# M_D_ext_power_8_0_1.net
KiCad netlist of a schematic drawn in EAGLE
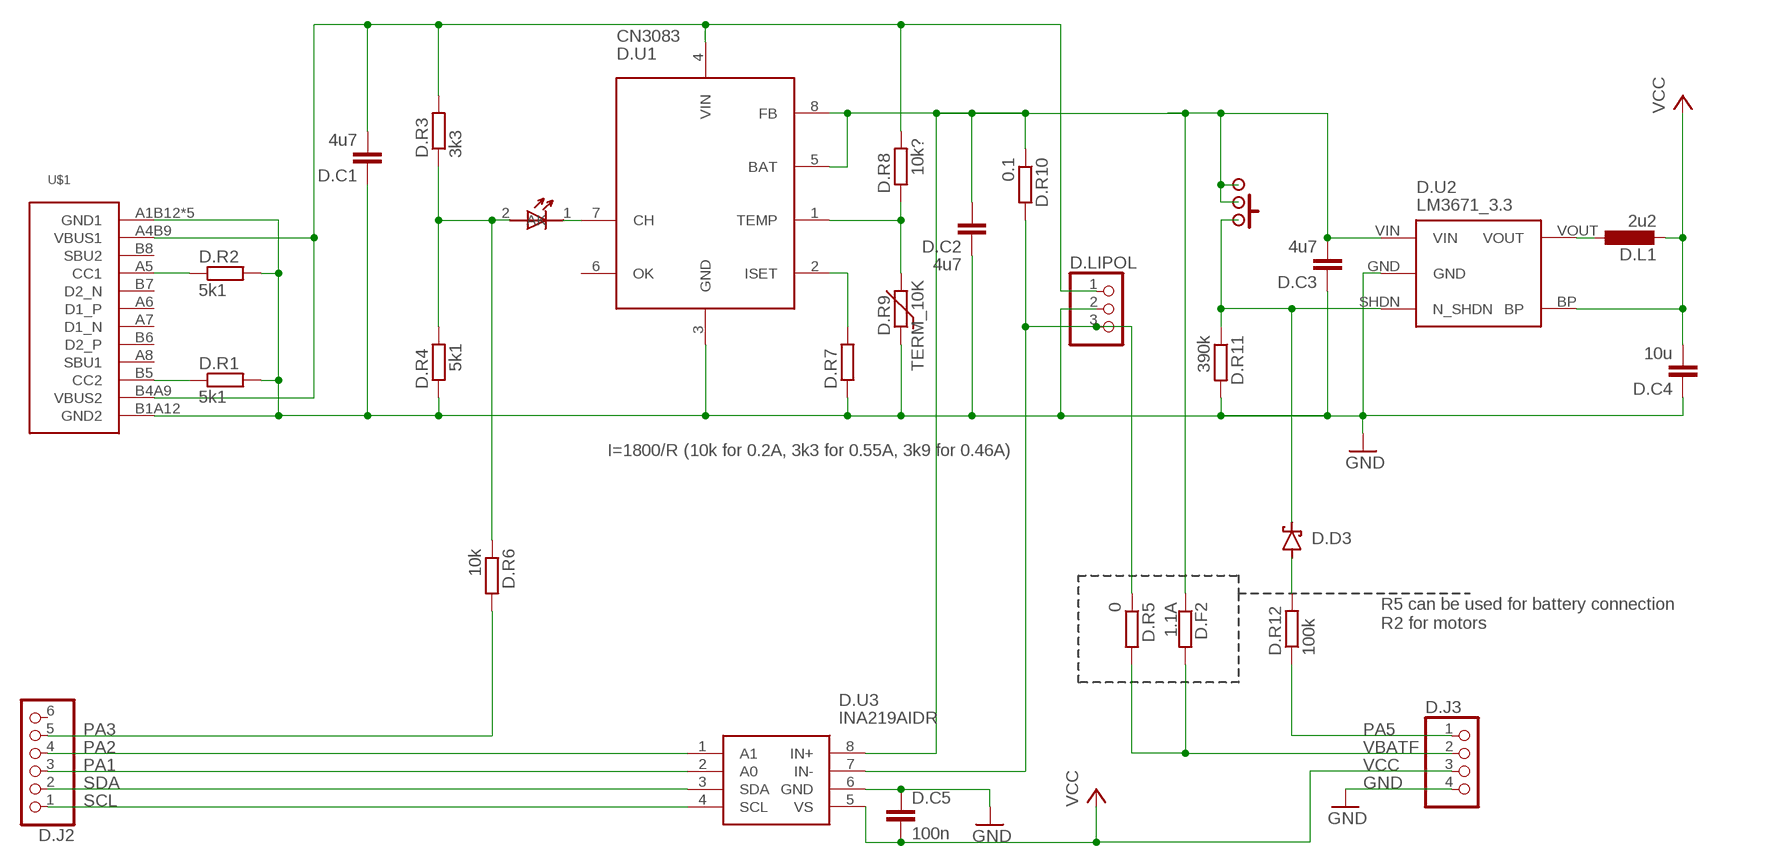
[diagram p0: schematic, sheet 1]

(export (version "E")
  (design (tool "Eeschema 10.0.6"))
  (components
    (comp (ref "D.C1")
      (value "4u7")
      (footprint "eagle-import:C0603")
      (libsource (lib "eagle-import") (part "C-EUC0603"))
    )
    (comp (ref "D.C2")
      (value "4u7")
      (footprint "eagle-import:C0603")
      (libsource (lib "eagle-import") (part "C-EUC0603"))
    )
    (comp (ref "D.C3")
      (value "4u7")
      (footprint "eagle-import:C0603")
      (libsource (lib "eagle-import") (part "C-EUC0603"))
    )
    (comp (ref "D.C4")
      (value "10u")
      (footprint "eagle-import:C0805")
      (libsource (lib "eagle-import") (part "C-EUC0805"))
    )
    (comp (ref "D.C5")
      (value "100n")
      (footprint "eagle-import:C0603")
      (libsource (lib "eagle-import") (part "C-EUC0603"))
    )
    (comp (ref "D.D1")
      (value "LED_1.8")
      (footprint "eagle-import:LED_1.8")
      (libsource (lib "eagle-import") (part "LED_1.8"))
    )
    (comp (ref "D.D3")
      (value "SHOTKY_2.8")
      (footprint "eagle-import:SHOTKY_2.8")
      (libsource (lib "eagle-import") (part "SHOTKY_2.8"))
    )
    (comp (ref "D.F2")
      (value "1.1A")
      (footprint "eagle-import:R0805")
      (libsource (lib "eagle-import") (part "R-EU_R0805"))
    )
    (comp (ref "D.J2")
      (value "PINHD-1X6")
      (footprint "eagle-import:1X06")
      (libsource (lib "eagle-import") (part "PINHD-1X6"))
    )
    (comp (ref "D.J3")
      (value "PINHD-1X4")
      (footprint "eagle-import:1X04")
      (libsource (lib "eagle-import") (part "PINHD-1X4"))
    )
    (comp (ref "D.L1")
      (value "2u2")
      (footprint "eagle-import:L3230M")
      (libsource (lib "eagle-import") (part "L-EUL3230M"))
    )
    (comp (ref "D.LIPOL")
      (value "PINHEAD-1X3-2")
      (footprint "eagle-import:1X-03-2")
      (libsource (lib "eagle-import") (part "PINHEAD-1X3-2"))
    )
    (comp (ref "D.ON/OFF/RESET")
      (value "SWITCH")
      (footprint "eagle-import:SWITCH")
      (libsource (lib "eagle-import") (part "SWITCH"))
    )
    (comp (ref "D.R1")
      (value "5k1")
      (footprint "eagle-import:R0603")
      (libsource (lib "eagle-import") (part "R-EU_R0603"))
    )
    (comp (ref "D.R2")
      (value "5k1")
      (footprint "eagle-import:R0603")
      (libsource (lib "eagle-import") (part "R-EU_R0603"))
    )
    (comp (ref "D.R3")
      (value "3k3")
      (footprint "eagle-import:R0603")
      (libsource (lib "eagle-import") (part "R-EU_R0603"))
    )
    (comp (ref "D.R4")
      (value "5k1")
      (footprint "eagle-import:R0603")
      (libsource (lib "eagle-import") (part "R-EU_R0603"))
    )
    (comp (ref "D.R5")
      (value "0")
      (footprint "eagle-import:R0603")
      (libsource (lib "eagle-import") (part "R-EU_R0603"))
    )
    (comp (ref "D.R6")
      (value "10k")
      (footprint "eagle-import:R0603")
      (libsource (lib "eagle-import") (part "R-EU_R0603"))
    )
    (comp (ref "D.R7")
      (value "I=1800/R (10k for 0.2A, 3k3 for 0.55A, 3k9 for 0.46A)")
      (footprint "eagle-import:R0603")
      (libsource (lib "eagle-import") (part "R-EU_R0603"))
    )
    (comp (ref "D.R8")
      (value "10k?")
      (footprint "eagle-import:R0603")
      (libsource (lib "eagle-import") (part "R-EU_R0603"))
    )
    (comp (ref "D.R9")
      (value "TERM_10K")
      (footprint "eagle-import:THERM")
      (libsource (lib "eagle-import") (part "THERM"))
    )
    (comp (ref "D.R10")
      (value "0.1")
      (footprint "eagle-import:R0805")
      (libsource (lib "eagle-import") (part "R-EU_R0805"))
    )
    (comp (ref "D.R11")
      (value "390k")
      (footprint "eagle-import:R0603")
      (libsource (lib "eagle-import") (part "R-EU_R0603"))
    )
    (comp (ref "D.R12")
      (value "100k")
      (footprint "eagle-import:R0603")
      (libsource (lib "eagle-import") (part "R-EU_R0603"))
    )
    (comp (ref "D.U1")
      (value "CN3083")
      (footprint "eagle-import:SOP8")
      (libsource (lib "eagle-import") (part "CN3083"))
    )
    (comp (ref "D.U2")
      (value "LM3671_3.3")
      (footprint "eagle-import:SOT32-5")
      (libsource (lib "eagle-import") (part "STABILISER_APE8865"))
    )
    (comp (ref "D.U3")
      (value "INA219AIDR")
      (footprint "eagle-import:SOIC127P600X175-8N")
      (fields (field (name "MOUSER_PART_NUMBER") "595-INA219AIDR"))
      (libsource (lib "eagle-import") (part "INA219AIDR"))
    )
    (comp (ref "U$1")
      (value "USB-C")
      (footprint "eagle-import:USB-C")
      (libsource (lib "eagle-import") (part "USB-C"))
    )
  )
  (nets
    (net (code "1") (name "/PA1") (class "Default")
      (node (ref "D.J2") (pin "3") (pinfunction "3_3") (pintype "passive"))
      (node (ref "D.U3") (pin "2") (pinfunction "A0_2") (pintype "bidirectional"))
    )
    (net (code "2") (name "/PA2") (class "Default")
      (node (ref "D.J2") (pin "4") (pinfunction "4_4") (pintype "passive"))
      (node (ref "D.U3") (pin "1") (pinfunction "A1_1") (pintype "bidirectional"))
    )
    (net (code "3") (name "/PA3") (class "Default")
      (node (ref "D.J2") (pin "5") (pinfunction "5_5") (pintype "passive"))
      (node (ref "D.R6") (pin "2") (pinfunction "2_2") (pintype "passive"))
    )
    (net (code "4") (name "/PA5") (class "Default")
      (node (ref "D.C1") (pin "2") (pinfunction "2_2") (pintype "passive"))
      (node (ref "D.LIPOL") (pin "1") (pinfunction "1_1") (pintype "passive"))
      (node (ref "D.R3") (pin "2") (pinfunction "2_2") (pintype "passive"))
      (node (ref "D.R8") (pin "2") (pinfunction "2_2") (pintype "passive"))
      (node (ref "D.U1") (pin "4") (pinfunction "VIN_4") (pintype "bidirectional"))
      (node (ref "U$1") (pin "A4B9") (pinfunction "VBUS1_A4B9") (pintype "bidirectional"))
      (node (ref "U$1") (pin "B4A9") (pinfunction "VBUS2_B4A9") (pintype "bidirectional"))
    )
    (net (code "5") (name "/SCL") (class "Default")
      (node (ref "D.J2") (pin "1") (pinfunction "1_1") (pintype "passive"))
      (node (ref "D.U3") (pin "4") (pinfunction "SCL_4") (pintype "bidirectional"))
    )
    (net (code "6") (name "/SDA") (class "Default")
      (node (ref "D.J2") (pin "2") (pinfunction "2_2") (pintype "passive"))
      (node (ref "D.U3") (pin "3") (pinfunction "SDA_3") (pintype "bidirectional"))
    )
    (net (code "7") (name "/VBATF") (class "Default")
      (node (ref "D.F2") (pin "2") (pinfunction "2_2") (pintype "passive"))
      (node (ref "D.J3") (pin "2") (pinfunction "2_2") (pintype "passive"))
      (node (ref "D.R5") (pin "2") (pinfunction "2_2") (pintype "passive"))
    )
    (net (code "8") (name "GND") (class "Default")
      (node (ref "D.C1") (pin "1") (pinfunction "1_1") (pintype "passive"))
      (node (ref "D.C2") (pin "1") (pinfunction "1_1") (pintype "passive"))
      (node (ref "D.C3") (pin "1") (pinfunction "1_1") (pintype "passive"))
      (node (ref "D.C4") (pin "1") (pinfunction "1_1") (pintype "passive"))
      (node (ref "D.C5") (pin "1") (pinfunction "1_1") (pintype "passive"))
      (node (ref "D.J3") (pin "4") (pinfunction "4_4") (pintype "passive"))
      (node (ref "D.LIPOL") (pin "2") (pinfunction "2_2") (pintype "passive"))
      (node (ref "D.R1") (pin "2") (pinfunction "2_2") (pintype "passive"))
      (node (ref "D.R11") (pin "2") (pinfunction "2_2") (pintype "passive"))
      (node (ref "D.R2") (pin "2") (pinfunction "2_2") (pintype "passive"))
      (node (ref "D.R4") (pin "1") (pinfunction "1_1") (pintype "passive"))
      (node (ref "D.R7") (pin "1") (pinfunction "1_1") (pintype "passive"))
      (node (ref "D.R9") (pin "1") (pinfunction "1_1") (pintype "passive"))
      (node (ref "D.U1") (pin "3") (pinfunction "GND_3") (pintype "bidirectional"))
      (node (ref "D.U2") (pin "GND") (pinfunction "GND_GND") (pintype "bidirectional"))
      (node (ref "D.U3") (pin "6") (pinfunction "GND_6") (pintype "bidirectional"))
      (node (ref "U$1") (pin "A1B12") (pinfunction "GND1_A1B12") (pintype "bidirectional"))
      (node (ref "U$1") (pin "B1A12") (pinfunction "GND2_B1A12") (pintype "bidirectional"))
      (node (ref "U$1") (pin "SH1") (pinfunction "GND1_SH1") (pintype "bidirectional"))
      (node (ref "U$1") (pin "SH2") (pinfunction "GND1_SH2") (pintype "bidirectional"))
      (node (ref "U$1") (pin "SH3") (pinfunction "GND1_SH3") (pintype "bidirectional"))
      (node (ref "U$1") (pin "SH4") (pinfunction "GND1_SH4") (pintype "bidirectional"))
    )
    (net (code "9") (name "Net-(D.D1-A)") (class "Default")
      (node (ref "D.D1") (pin "2") (pinfunction "A_2") (pintype "bidirectional"))
      (node (ref "D.R3") (pin "1") (pinfunction "1_1") (pintype "passive"))
      (node (ref "D.R4") (pin "2") (pinfunction "2_2") (pintype "passive"))
      (node (ref "D.R6") (pin "1") (pinfunction "1_1") (pintype "passive"))
    )
    (net (code "10") (name "Net-(D.D1-K)") (class "Default")
      (node (ref "D.D1") (pin "1") (pinfunction "K_1") (pintype "bidirectional"))
      (node (ref "D.U1") (pin "7") (pinfunction "CH_7") (pintype "bidirectional"))
    )
    (net (code "11") (name "Net-(D.D3-C)") (class "Default")
      (node (ref "D.D3") (pin "K") (pinfunction "C_K") (pintype "passive"))
      (node (ref "D.ON/OFF/RESET") (pin "P$1") (pinfunction "P$1_P$1") (pintype "bidirectional"))
      (node (ref "D.ON/OFF/RESET") (pin "P$5") (pinfunction "P$1_P$5") (pintype "bidirectional"))
      (node (ref "D.ON/OFF/RESET") (pin "P$7") (pinfunction "P$1_P$7") (pintype "bidirectional"))
      (node (ref "D.R11") (pin "1") (pinfunction "1_1") (pintype "passive"))
      (node (ref "D.U2") (pin "SHDN") (pinfunction "N_SHDN_SHDN") (pintype "bidirectional"))
    )
    (net (code "12") (name "Net-(D.D3-PadA)") (class "Default")
      (node (ref "D.D3") (pin "A") (pinfunction "A_A") (pintype "passive"))
      (node (ref "D.R12") (pin "2") (pinfunction "2_2") (pintype "passive"))
    )
    (net (code "13") (name "Net-(D.J3-Pad1)") (class "Default")
      (node (ref "D.J3") (pin "1") (pinfunction "1_1") (pintype "passive"))
      (node (ref "D.R12") (pin "1") (pinfunction "1_1") (pintype "passive"))
    )
    (net (code "14") (name "Net-(D.L1-Pad1)") (class "Default")
      (node (ref "D.L1") (pin "1") (pinfunction "1_1") (pintype "passive"))
      (node (ref "D.U2") (pin "VOUT") (pinfunction "VOUT_VOUT") (pintype "bidirectional"))
    )
    (net (code "15") (name "Net-(D.U1-BAT)") (class "Default")
      (node (ref "D.C2") (pin "2") (pinfunction "2_2") (pintype "passive"))
      (node (ref "D.C3") (pin "2") (pinfunction "2_2") (pintype "passive"))
      (node (ref "D.F2") (pin "1") (pinfunction "1_1") (pintype "passive"))
      (node (ref "D.ON/OFF/RESET") (pin "P$2") (pinfunction "P$2_P$2") (pintype "bidirectional"))
      (node (ref "D.ON/OFF/RESET") (pin "P$3") (pinfunction "P$3_P$3") (pintype "bidirectional"))
      (node (ref "D.ON/OFF/RESET") (pin "P$4") (pinfunction "P$3_P$4") (pintype "bidirectional"))
      (node (ref "D.ON/OFF/RESET") (pin "P$6") (pinfunction "P$3_P$6") (pintype "bidirectional"))
      (node (ref "D.R10") (pin "1") (pinfunction "1_1") (pintype "passive"))
      (node (ref "D.U1") (pin "5") (pinfunction "BAT_5") (pintype "bidirectional"))
      (node (ref "D.U1") (pin "8") (pinfunction "FB_8") (pintype "bidirectional"))
      (node (ref "D.U2") (pin "VIN") (pinfunction "VIN_VIN") (pintype "bidirectional"))
      (node (ref "D.U3") (pin "8") (pinfunction "IN+_8") (pintype "bidirectional"))
    )
    (net (code "16") (name "Net-(D.U1-ISET)") (class "Default")
      (node (ref "D.R7") (pin "2") (pinfunction "2_2") (pintype "passive"))
      (node (ref "D.U1") (pin "2") (pinfunction "ISET_2") (pintype "bidirectional"))
    )
    (net (code "17") (name "Net-(D.U1-TEMP)") (class "Default")
      (node (ref "D.R8") (pin "1") (pinfunction "1_1") (pintype "passive"))
      (node (ref "D.R9") (pin "2") (pinfunction "2_2") (pintype "passive"))
      (node (ref "D.U1") (pin "1") (pinfunction "TEMP_1") (pintype "bidirectional"))
    )
    (net (code "18") (name "Net-(D.U3-IN-)") (class "Default")
      (node (ref "D.LIPOL") (pin "3") (pinfunction "3_3") (pintype "passive"))
      (node (ref "D.R10") (pin "2") (pinfunction "2_2") (pintype "passive"))
      (node (ref "D.R5") (pin "1") (pinfunction "1_1") (pintype "passive"))
      (node (ref "D.U3") (pin "7") (pinfunction "IN-_7") (pintype "bidirectional"))
    )
    (net (code "19") (name "Net-(U$1-CC1)") (class "Default")
      (node (ref "D.R2") (pin "1") (pinfunction "1_1") (pintype "passive"))
      (node (ref "U$1") (pin "A5") (pinfunction "CC1_A5") (pintype "bidirectional"))
    )
    (net (code "20") (name "Net-(U$1-CC2)") (class "Default")
      (node (ref "D.R1") (pin "1") (pinfunction "1_1") (pintype "passive"))
      (node (ref "U$1") (pin "B5") (pinfunction "CC2_B5") (pintype "bidirectional"))
    )
    (net (code "21") (name "VCC") (class "Default")
      (node (ref "D.C4") (pin "2") (pinfunction "2_2") (pintype "passive"))
      (node (ref "D.C5") (pin "2") (pinfunction "2_2") (pintype "passive"))
      (node (ref "D.J3") (pin "3") (pinfunction "3_3") (pintype "passive"))
      (node (ref "D.L1") (pin "2") (pinfunction "2_2") (pintype "passive"))
      (node (ref "D.U2") (pin "BP") (pinfunction "BP_BP") (pintype "bidirectional"))
      (node (ref "D.U3") (pin "5") (pinfunction "VS_5") (pintype "bidirectional"))
    )
    (net (code "22") (name "unconnected-(D.J2-Pad6)") (class "Default")
      (node (ref "D.J2") (pin "6") (pinfunction "6_6") (pintype "passive"))
    )
    (net (code "23") (name "unconnected-(D.U1-OK-Pad6)") (class "Default")
      (node (ref "D.U1") (pin "6") (pinfunction "OK_6") (pintype "bidirectional"))
    )
    (net (code "24") (name "unconnected-(U$1-D1_N-PadA7)") (class "Default")
      (node (ref "U$1") (pin "A7") (pinfunction "D1_N_A7") (pintype "bidirectional"))
    )
    (net (code "25") (name "unconnected-(U$1-D1_P-PadA6)") (class "Default")
      (node (ref "U$1") (pin "A6") (pinfunction "D1_P_A6") (pintype "bidirectional"))
    )
    (net (code "26") (name "unconnected-(U$1-D2_N-PadB7)") (class "Default")
      (node (ref "U$1") (pin "B7") (pinfunction "D2_N_B7") (pintype "bidirectional"))
    )
    (net (code "27") (name "unconnected-(U$1-D2_P-PadB6)") (class "Default")
      (node (ref "U$1") (pin "B6") (pinfunction "D2_P_B6") (pintype "bidirectional"))
    )
    (net (code "28") (name "unconnected-(U$1-SBU1-PadA8)") (class "Default")
      (node (ref "U$1") (pin "A8") (pinfunction "SBU1_A8") (pintype "bidirectional"))
    )
    (net (code "29") (name "unconnected-(U$1-SBU2-PadB8)") (class "Default")
      (node (ref "U$1") (pin "B8") (pinfunction "SBU2_B8") (pintype "bidirectional"))
    )
  )
)
